# rfm69_carrier.net
KiCad netlist of a schematic drawn in EAGLE
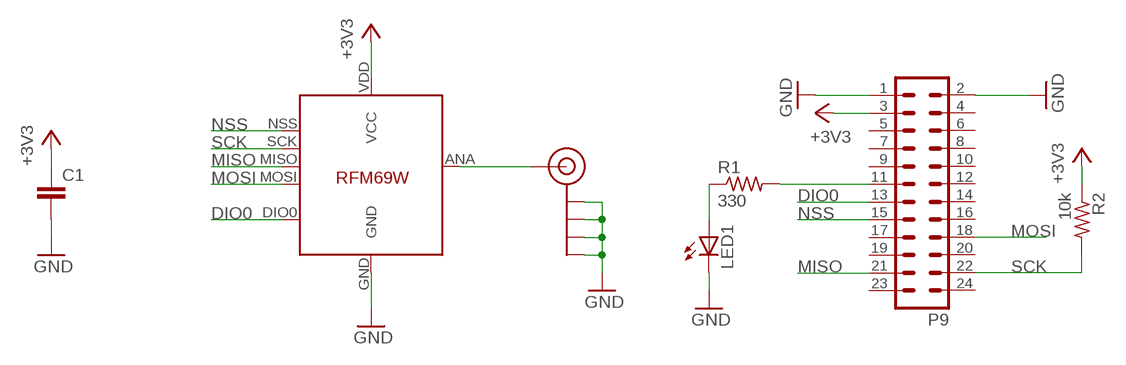
[diagram p0: schematic, sheet 1]

(export (version "E")
  (design (tool "Eeschema 10.0.6"))
  (components
    (comp (ref "ANT")
      (value "SMA_EDGE")
      (footprint "eagle-import:SMA-EDGE")
      (libsource (lib "eagle-import") (part "SMA_EDGE"))
    )
    (comp (ref "C1")
      (value "C-EUC1206")
      (footprint "eagle-import:C1206")
      (libsource (lib "eagle-import") (part "C-EUC1206"))
    )
    (comp (ref "LED1")
      (value "LEDCHIP-LED0805")
      (footprint "eagle-import:CHIP-LED0805")
      (libsource (lib "eagle-import") (part "LEDCHIP-LED0805"))
    )
    (comp (ref "P9")
      (value "MA12-2")
      (footprint "eagle-import:MA12-2")
      (libsource (lib "eagle-import") (part "MA12-2"))
    )
    (comp (ref "R1")
      (value "330")
      (footprint "eagle-import:R0603")
      (libsource (lib "eagle-import") (part "R-US_R0603"))
    )
    (comp (ref "R2")
      (value "10k")
      (footprint "eagle-import:R0603")
      (libsource (lib "eagle-import") (part "R-US_R0603"))
    )
    (comp (ref "U1")
      (value "RFM69")
      (footprint "eagle-import:RFM69W-MINPADS")
      (libsource (lib "eagle-import") (part "RFM69"))
    )
  )
  (nets
    (net (code "1") (name "+3V3") (class "Default")
      (node (ref "C1") (pin "1") (pinfunction "1_1") (pintype "passive"))
      (node (ref "P9") (pin "3") (pinfunction "3_3") (pintype "passive"))
      (node (ref "R2") (pin "1") (pinfunction "1_1") (pintype "passive"))
      (node (ref "U1") (pin "VDD") (pinfunction "VCC_VDD") (pintype "power_in"))
    )
    (net (code "2") (name "/DIO0") (class "Default")
      (node (ref "P9") (pin "13") (pinfunction "13_13") (pintype "passive"))
      (node (ref "U1") (pin "DIO0") (pinfunction "DIO0_DIO0") (pintype "open_collector"))
    )
    (net (code "3") (name "/MISO") (class "Default")
      (node (ref "P9") (pin "21") (pinfunction "21_21") (pintype "passive"))
      (node (ref "U1") (pin "MISO") (pinfunction "MISO_MISO") (pintype "input"))
    )
    (net (code "4") (name "/MOSI") (class "Default")
      (node (ref "P9") (pin "18") (pinfunction "18_18") (pintype "passive"))
      (node (ref "U1") (pin "MOSI") (pinfunction "MOSI_MOSI") (pintype "output"))
    )
    (net (code "5") (name "/NSS") (class "Default")
      (node (ref "P9") (pin "15") (pinfunction "15_15") (pintype "passive"))
      (node (ref "U1") (pin "NSS") (pinfunction "SEL_NSS") (pintype "input"))
    )
    (net (code "6") (name "/SCK") (class "Default")
      (node (ref "P9") (pin "22") (pinfunction "22_22") (pintype "passive"))
      (node (ref "R2") (pin "2") (pinfunction "2_2") (pintype "passive"))
      (node (ref "U1") (pin "SCK") (pinfunction "SCK_SCK") (pintype "input"))
    )
    (net (code "7") (name "GND") (class "Default")
      (node (ref "ANT") (pin "GND@0") (pinfunction "GND_GND@0") (pintype "bidirectional"))
      (node (ref "ANT") (pin "GND@1") (pinfunction "GND_GND@1") (pintype "bidirectional"))
      (node (ref "ANT") (pin "GND@2") (pinfunction "GND_GND@2") (pintype "bidirectional"))
      (node (ref "ANT") (pin "GND@3") (pinfunction "GND_GND@3") (pintype "bidirectional"))
      (node (ref "C1") (pin "2") (pinfunction "2_2") (pintype "passive"))
      (node (ref "LED1") (pin "C") (pinfunction "C_C") (pintype "passive"))
      (node (ref "P9") (pin "1") (pinfunction "1_1") (pintype "passive"))
      (node (ref "P9") (pin "2") (pinfunction "2_2") (pintype "passive"))
      (node (ref "U1") (pin "GND") (pinfunction "GND_GND") (pintype "power_in"))
    )
    (net (code "8") (name "Net-(ANT-SIGNAL)") (class "Default")
      (node (ref "ANT") (pin "SIG") (pinfunction "SIGNAL_SIG") (pintype "bidirectional"))
      (node (ref "U1") (pin "ANA") (pinfunction "ANT_ANA") (pintype "passive"))
    )
    (net (code "9") (name "Net-(LED1-PadA)") (class "Default")
      (node (ref "LED1") (pin "A") (pinfunction "A_A") (pintype "passive"))
      (node (ref "R1") (pin "1") (pinfunction "1_1") (pintype "passive"))
    )
    (net (code "10") (name "Net-(P9-Pad11)") (class "Default")
      (node (ref "P9") (pin "11") (pinfunction "11_11") (pintype "passive"))
      (node (ref "R1") (pin "2") (pinfunction "2_2") (pintype "passive"))
    )
    (net (code "11") (name "unconnected-(P9-Pad4)") (class "Default")
      (node (ref "P9") (pin "4") (pinfunction "4_4") (pintype "passive"))
    )
    (net (code "12") (name "unconnected-(P9-Pad5)") (class "Default")
      (node (ref "P9") (pin "5") (pinfunction "5_5") (pintype "passive"))
    )
    (net (code "13") (name "unconnected-(P9-Pad6)") (class "Default")
      (node (ref "P9") (pin "6") (pinfunction "6_6") (pintype "passive"))
    )
    (net (code "14") (name "unconnected-(P9-Pad7)") (class "Default")
      (node (ref "P9") (pin "7") (pinfunction "7_7") (pintype "passive"))
    )
    (net (code "15") (name "unconnected-(P9-Pad8)") (class "Default")
      (node (ref "P9") (pin "8") (pinfunction "8_8") (pintype "passive"))
    )
    (net (code "16") (name "unconnected-(P9-Pad9)") (class "Default")
      (node (ref "P9") (pin "9") (pinfunction "9_9") (pintype "passive"))
    )
    (net (code "17") (name "unconnected-(P9-Pad10)") (class "Default")
      (node (ref "P9") (pin "10") (pinfunction "10_10") (pintype "passive"))
    )
    (net (code "18") (name "unconnected-(P9-Pad12)") (class "Default")
      (node (ref "P9") (pin "12") (pinfunction "12_12") (pintype "passive"))
    )
    (net (code "19") (name "unconnected-(P9-Pad14)") (class "Default")
      (node (ref "P9") (pin "14") (pinfunction "14_14") (pintype "passive"))
    )
    (net (code "20") (name "unconnected-(P9-Pad16)") (class "Default")
      (node (ref "P9") (pin "16") (pinfunction "16_16") (pintype "passive"))
    )
    (net (code "21") (name "unconnected-(P9-Pad17)") (class "Default")
      (node (ref "P9") (pin "17") (pinfunction "17_17") (pintype "passive"))
    )
    (net (code "22") (name "unconnected-(P9-Pad19)") (class "Default")
      (node (ref "P9") (pin "19") (pinfunction "19_19") (pintype "passive"))
    )
    (net (code "23") (name "unconnected-(P9-Pad20)") (class "Default")
      (node (ref "P9") (pin "20") (pinfunction "20_20") (pintype "passive"))
    )
    (net (code "24") (name "unconnected-(P9-Pad23)") (class "Default")
      (node (ref "P9") (pin "23") (pinfunction "23_23") (pintype "passive"))
    )
    (net (code "25") (name "unconnected-(P9-Pad24)") (class "Default")
      (node (ref "P9") (pin "24") (pinfunction "24_24") (pintype "passive"))
    )
  )
)
